# Main.net
KiCad netlist of a schematic drawn in Altium Designer
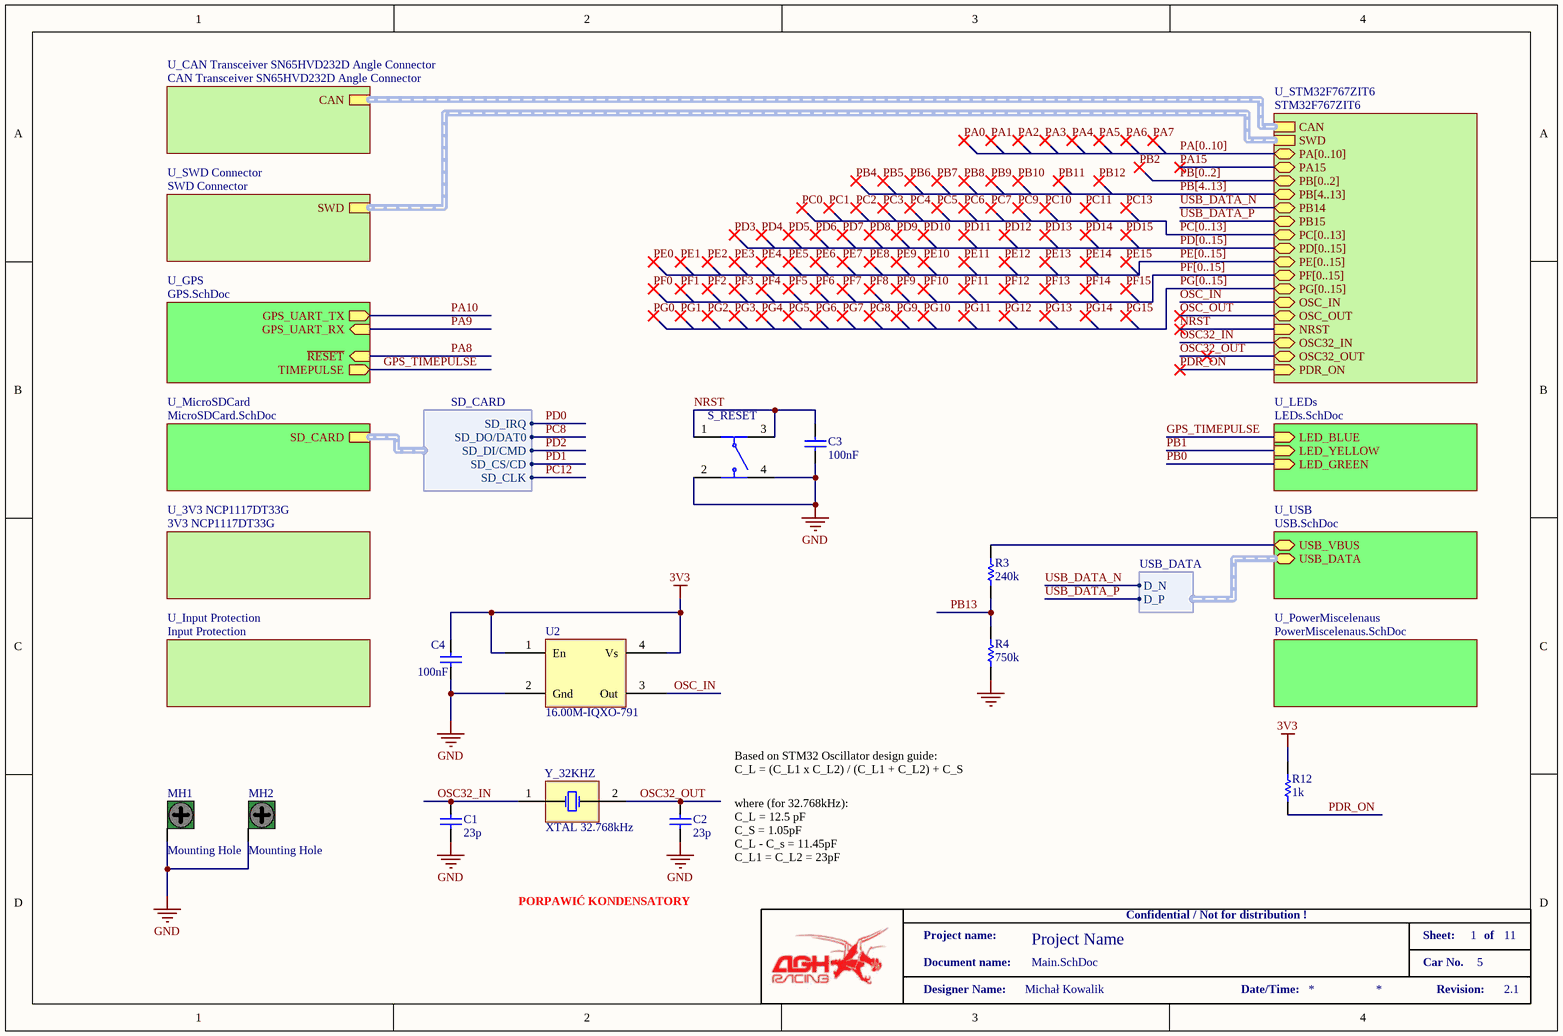
[diagram p0: Main.SchDoc]

(export (version "E")
  (design (tool "Eeschema 10.0.6"))
  (components
    (comp (ref "C1")
      (value "23p")
      (footprint "agh_racing_2018:CAP_0603_IPC_MD")
      (description "Capacitor")
      (fields (field (name "Comment") "Cap"))
      (libsource (lib "agh_racing_2018") (part "Cap"))
    )
    (comp (ref "C2")
      (value "23p")
      (footprint "agh_racing_2018:CAP_0603_IPC_MD")
      (description "Capacitor")
      (fields (field (name "Comment") "Cap"))
      (libsource (lib "agh_racing_2018") (part "Cap"))
    )
    (comp (ref "C3")
      (value "100nF")
      (footprint "agh_racing_2018:CAP_0603_IPC_MD")
      (description "Capacitor")
      (fields (field (name "Comment") "Cap"))
      (libsource (lib "agh_racing_2018") (part "Cap"))
    )
    (comp (ref "C4")
      (value "100nF")
      (footprint "agh_racing_2018:CAP_0603_IPC_MD")
      (description "Capacitor")
      (fields (field (name "Comment") "Cap"))
      (libsource (lib "agh_racing_2018") (part "Cap"))
    )
    (comp (ref "MH1")
      (value "Mounting Hole")
      (footprint "agh_racing_2018:MOUNTING HOLE 2mm")
      (libsource (lib "agh_racing_2018") (part "Mounting Hole"))
    )
    (comp (ref "MH2")
      (value "Mounting Hole")
      (footprint "agh_racing_2018:MOUNTING HOLE 2mm")
      (libsource (lib "agh_racing_2018") (part "Mounting Hole"))
    )
    (comp (ref "R3")
      (value "240k")
      (footprint "agh_racing_2018:RES_0603_IPC_MD")
      (description "Resistor")
      (fields (field (name "Comment") "Res"))
      (libsource (lib "agh_racing_2018") (part "Res"))
    )
    (comp (ref "R4")
      (value "750k")
      (footprint "agh_racing_2018:RES_0603_IPC_MD")
      (description "Resistor")
      (fields (field (name "Comment") "Res"))
      (libsource (lib "agh_racing_2018") (part "Res"))
    )
    (comp (ref "R12")
      (value "1k")
      (footprint "agh_racing_2018:RES_0603_IPC_MD")
      (description "Resistor")
      (fields (field (name "Comment") "Res"))
      (libsource (lib "agh_racing_2018") (part "Res"))
    )
    (comp (ref "S_RESET")
      (value "Switch")
      (footprint "agh_racing_2018:Microswitch_SMD_4_3mm")
      (libsource (lib "agh_racing_2018") (part "Microswitch"))
    )
    (comp (ref "U2")
      (value "16.00M-IQXO-791")
      (footprint "ICLCX18")
      (description "Crystal Clock Oscillator")
      (fields
        (field (name "MANUFACTURER") "IQD FREQUENCY PRODUCTS")
        (field (name "MPN") "LFSPXO066657CUTT")
        (field (name "NAME") "16.00M-IQXO-791")
      )
      (libsource (lib "agh_racing_2018_temp") (part "16.00M-IQXO-791"))
    )
    (comp (ref "Y_32KHZ")
      (value "XTAL 32.768kHz")
      (footprint "XTAL 32.768kHz IQD Frequencies")
      (description "Crystal Oscillator 32.768kHz")
      (fields (field (name "MANUFACTURER") "IQD FREQUENCY PRODUCTS"))
      (libsource (lib "agh_racing_2018") (part "XTAL 32.768kHz 2-pin"))
    )
  )
  (nets
    (net (code "5") (name "/NRST") (class "Default")
      (node (ref "C3") (pin "2") (pinfunction "2_2") (pintype "passive"))
      (node (ref "S_RESET") (pin "1") (pinfunction "1_1") (pintype "passive"))
      (node (ref "S_RESET") (pin "3") (pinfunction "3_3") (pintype "passive"))
    )
    (net (code "6") (name "/OSC32_IN") (class "Default")
      (node (ref "C1") (pin "2") (pinfunction "2_2") (pintype "passive"))
      (node (ref "Y_32KHZ") (pin "1") (pinfunction "OSC1_1") (pintype "passive"))
    )
    (net (code "7") (name "/OSC32_OUT") (class "Default")
      (node (ref "C2") (pin "2") (pinfunction "2_2") (pintype "passive"))
      (node (ref "Y_32KHZ") (pin "2") (pinfunction "OSC2_2") (pintype "passive"))
    )
    (net (code "8") (name "/OSC_IN") (class "Default")
      (node (ref "U2") (pin "3") (pinfunction "Out_3") (pintype "passive"))
    )
    (net (code "35") (name "/PB13") (class "Default")
      (node (ref "R3") (pin "1") (pinfunction "1_1") (pintype "passive"))
      (node (ref "R4") (pin "2") (pinfunction "2_2") (pintype "passive"))
    )
    (net (code "68") (name "/PDR_ON") (class "Default")
      (node (ref "R12") (pin "1") (pinfunction "1_1") (pintype "passive"))
    )
    (net (code "124") (name "/USB_VBUS") (class "Default")
      (node (ref "R3") (pin "2") (pinfunction "2_2") (pintype "passive"))
    )
    (net (code "127") (name "3V3") (class "Default")
      (node (ref "C4") (pin "2") (pinfunction "2_2") (pintype "passive"))
      (node (ref "R12") (pin "2") (pinfunction "2_2") (pintype "passive"))
      (node (ref "U2") (pin "1") (pinfunction "En_1") (pintype "passive"))
      (node (ref "U2") (pin "4") (pinfunction "Vs_4") (pintype "passive"))
    )
    (net (code "128") (name "GND") (class "Default")
      (node (ref "C1") (pin "1") (pinfunction "1_1") (pintype "passive"))
      (node (ref "C2") (pin "1") (pinfunction "1_1") (pintype "passive"))
      (node (ref "C3") (pin "1") (pinfunction "1_1") (pintype "passive"))
      (node (ref "C4") (pin "1") (pinfunction "1_1") (pintype "passive"))
      (node (ref "MH1") (pin "MOUNTING") (pinfunction "MOUNTING_MOUNTING") (pintype "passive"))
      (node (ref "MH2") (pin "MOUNTING") (pinfunction "MOUNTING_MOUNTING") (pintype "passive"))
      (node (ref "R4") (pin "1") (pinfunction "1_1") (pintype "passive"))
      (node (ref "S_RESET") (pin "2") (pinfunction "2_2") (pintype "passive"))
      (node (ref "S_RESET") (pin "4") (pinfunction "4_4") (pintype "passive"))
      (node (ref "U2") (pin "2") (pinfunction "Gnd_2") (pintype "passive"))
    )
  )
)
